# jtag.net
KiCad netlist of a schematic drawn in Altium Designer
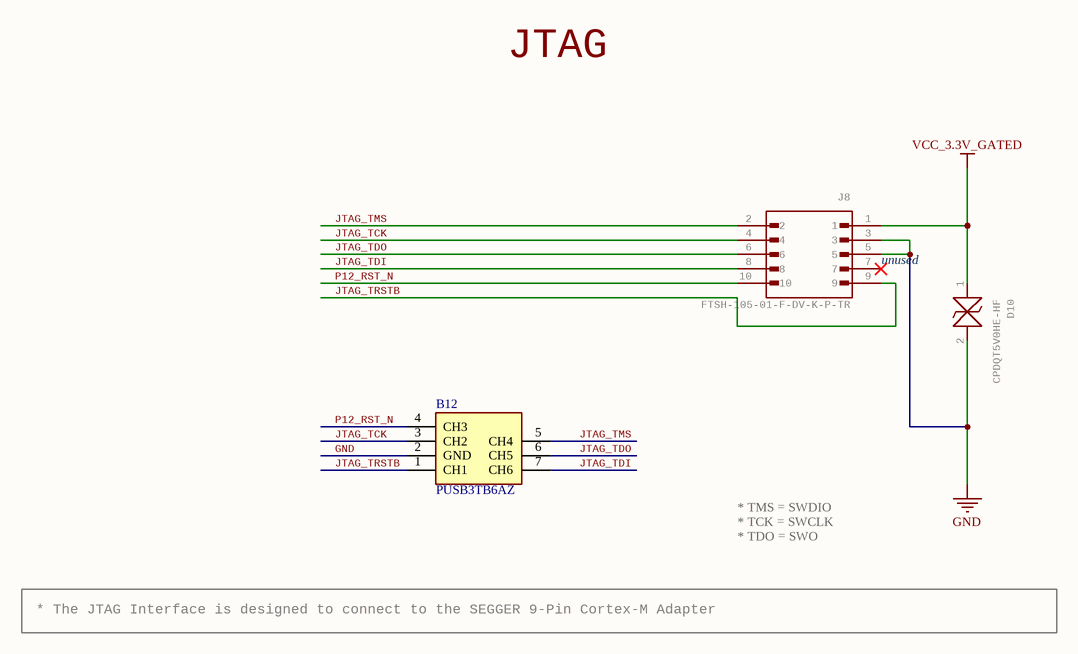
[diagram p0: jtag.SchDoc]

(export (version "E")
  (design (tool "Eeschema 10.0.6"))
  (components
    (comp (ref "B12")
      (value "PUSB3TB6AZ")
      (footprint "PUSB3TB6AZ")
      (description "NEXPERIA - PUSB3TB6AZ - DIODE, ESD PROTECTION, 5.5V, 0.27PF")
      (fields (field (name "MOUSER PART NUMBER") "771-PUSB3TB6AZ"))
      (libsource (lib "PUSB3TB6AZ") (part "PUSB3TB6AZ"))
    )
    (comp (ref "D10")
      (value "CPDQT5V0HE-HF")
      (footprint "CPDQT5V0HEHF")
      (description "ESD Suppressors / TVS Diodes DIODE ESD 5VWM 65W 0402/SOD-923F   Source:  Datasheet")
      (fields (field (name "MOUSER_PART_NUMBER") "MOUSER_PART_NUMBER"))
      (libsource (lib "rt10") (part "CPDQT5V0HE-HF"))
    )
    (comp (ref "J8")
      (value "FTSH-105-01-F-DV-K-P-TR")
      (footprint "CNC_3221-10-0300-00")
      (description "Check availability")
      (fields (field (name "MF") "CNC Tech"))
      (libsource (lib "rt10") (part "3221-10-0300-00"))
    )
  )
  (nets
    (net (code "1") (name "/JTAG_TCK") (class "Default")
      (node (ref "B12") (pin "3") (pinfunction "CH2_3") (pintype "passive"))
      (node (ref "J8") (pin "4") (pinfunction "4_4") (pintype "passive"))
    )
    (net (code "2") (name "/JTAG_TDI") (class "Default")
      (node (ref "B12") (pin "7") (pinfunction "CH6_7") (pintype "passive"))
      (node (ref "J8") (pin "8") (pinfunction "8_8") (pintype "passive"))
    )
    (net (code "3") (name "/JTAG_TDO") (class "Default")
      (node (ref "B12") (pin "6") (pinfunction "CH5_6") (pintype "passive"))
      (node (ref "J8") (pin "6") (pinfunction "6_6") (pintype "passive"))
    )
    (net (code "4") (name "/JTAG_TMS") (class "Default")
      (node (ref "B12") (pin "5") (pinfunction "CH4_5") (pintype "passive"))
      (node (ref "J8") (pin "2") (pinfunction "2_2") (pintype "passive"))
    )
    (net (code "5") (name "/JTAG_TRSTB") (class "Default")
      (node (ref "B12") (pin "1") (pinfunction "CH1_1") (pintype "passive"))
      (node (ref "J8") (pin "9") (pinfunction "9_9") (pintype "passive"))
    )
    (net (code "6") (name "/P12_RST_N") (class "Default")
      (node (ref "B12") (pin "4") (pinfunction "CH3_4") (pintype "passive"))
      (node (ref "J8") (pin "10") (pinfunction "10_10") (pintype "passive"))
    )
    (net (code "7") (name "GND") (class "Default")
      (node (ref "B12") (pin "2") (pinfunction "GND_2") (pintype "passive"))
      (node (ref "D10") (pin "2") (pinfunction "2_2") (pintype "bidirectional"))
      (node (ref "J8") (pin "3") (pinfunction "3_3") (pintype "passive"))
      (node (ref "J8") (pin "5") (pinfunction "5_5") (pintype "passive"))
    )
    (net (code "8") (name "VCC_3.3V_GATED") (class "Default")
      (node (ref "D10") (pin "1") (pinfunction "1_1") (pintype "bidirectional"))
      (node (ref "J8") (pin "1") (pinfunction "1_1") (pintype "passive"))
    )
    (net (code "9") (name "unconnected-(J8-Pad7)") (class "Default")
      (node (ref "J8") (pin "7") (pinfunction "7_7") (pintype "passive+no_connect"))
    )
  )
)
